# Project_MachNguon.net
KiCad netlist of a schematic drawn in Altium Designer
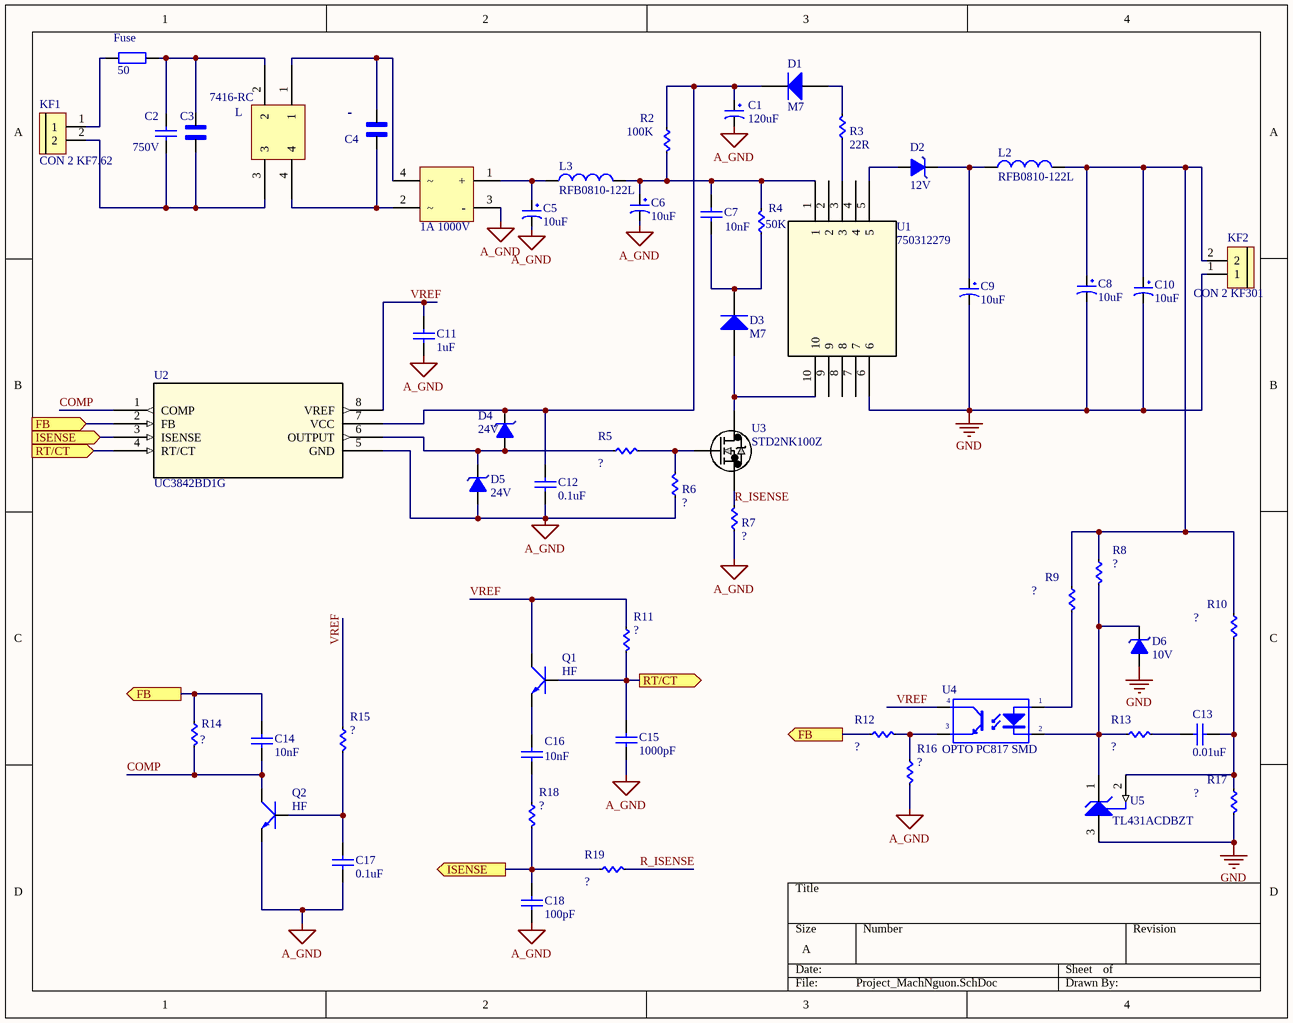
[diagram p0: Project_MachNguon.SchDoc]

(export (version "E")
  (design (tool "Eeschema 10.0.6"))
  (components
    (comp (ref "1")
      (value "1A 1000V")
      (footprint "DIODE CAU 1A SMD SOP4")
      (description "Dán")
      (libsource (lib "Altium_Lib_by_KhueNguyenCreator") (part "Diode CAU 1A SMD"))
    )
    (comp (ref "C1")
      (value "120uF")
      (footprint "tu hoa 5mm")
      (description "Cắm")
      (libsource (lib "Altium_Lib_by_KhueNguyenCreator") (part "Tu Hoa 100uF 25V 6x11"))
    )
    (comp (ref "C2")
      (value "750V")
      (footprint "tu tantalum dip5.08")
      (description "Cắm")
      (libsource (lib "Altium_Lib_by_KhueNguyenCreator") (part "Tu tantalum 100pF DIP5.08"))
    )
    (comp (ref "C3")
      (value "B32923P3155K000")
      (footprint "CAPRR2250W80L2650T1450H2950")
      (description "SUPPRESSION CAP, 1.5UF, CLASS X2, 305VAC ROHS COMPLIANT: YES")
      (fields (field (name "MF") "TDK Electronics"))
      (libsource (lib "Hung_lib") (part "B32923P3155K000"))
    )
    (comp (ref "C4")
      (value "B32923P3155K000")
      (footprint "CAPRR2250W80L2650T1450H2950")
      (description "SUPPRESSION CAP, 1.5UF, CLASS X2, 305VAC ROHS COMPLIANT: YES")
      (fields (field (name "MF") "TDK Electronics"))
      (libsource (lib "Hung_lib") (part "B32923P3155K000"))
    )
    (comp (ref "C5")
      (value "10uF")
      (footprint "tu Hoa 18mm")
      (description "Cắm")
      (libsource (lib "Altium_Lib_by_KhueNguyenCreator") (part "Tu Hoa 100uF 450V 18x35"))
    )
    (comp (ref "C6")
      (value "10uF")
      (footprint "tu Hoa 18mm")
      (description "Cắm")
      (libsource (lib "Altium_Lib_by_KhueNguyenCreator") (part "Tu Hoa 100uF 450V 18x35"))
    )
    (comp (ref "C7")
      (value "10nF")
      (footprint "tu 0603")
      (description "Dán")
      (libsource (lib "Altium_Lib_by_KhueNguyenCreator") (part "Tu 0603 105 50V 10%"))
    )
    (comp (ref "C8")
      (value "10uF")
      (footprint "tu hoa 10mm")
      (description "Cắm")
      (libsource (lib "Altium_Lib_by_KhueNguyenCreator") (part "Tu Hoa 1000uF 10V 10x12"))
    )
    (comp (ref "C9")
      (value "10uF")
      (footprint "tu hoa 10mm")
      (description "Cắm")
      (libsource (lib "Altium_Lib_by_KhueNguyenCreator") (part "Tu Hoa 1000uF 10V 10x12"))
    )
    (comp (ref "C10")
      (value "10uF")
      (footprint "tu hoa 10mm")
      (description "Cắm")
      (libsource (lib "Altium_Lib_by_KhueNguyenCreator") (part "Tu Hoa 1000uF 10V 10x12"))
    )
    (comp (ref "C11")
      (value "1uF")
      (footprint "tu 0603")
      (description "Dán")
      (libsource (lib "Altium_Lib_by_KhueNguyenCreator") (part "Tu 0603 101 50V 10%"))
    )
    (comp (ref "C12")
      (value "0.1uF")
      (footprint "tu 0603")
      (description "Dán")
      (libsource (lib "Altium_Lib_by_KhueNguyenCreator") (part "Tu 0603 101 50V 10%"))
    )
    (comp (ref "C13")
      (value "0.01uF")
      (footprint "tu 0603")
      (description "Dán")
      (libsource (lib "Altium_Lib_by_KhueNguyenCreator") (part "Tu 0603 101 50V 10%"))
    )
    (comp (ref "C14")
      (value "10nF")
      (footprint "tu 0603")
      (description "Dán")
      (libsource (lib "Altium_Lib_by_KhueNguyenCreator") (part "Tu 0603 101 50V 10%"))
    )
    (comp (ref "C15")
      (value "1000pF")
      (footprint "tu 0603")
      (description "Dán")
      (libsource (lib "Altium_Lib_by_KhueNguyenCreator") (part "Tu 0603 101 50V 10%"))
    )
    (comp (ref "C16")
      (value "10nF")
      (footprint "tu 0603")
      (description "Dán")
      (libsource (lib "Altium_Lib_by_KhueNguyenCreator") (part "Tu 0603 101 50V 10%"))
    )
    (comp (ref "C17")
      (value "0.1uF")
      (footprint "tu 0603")
      (description "Dán")
      (libsource (lib "Altium_Lib_by_KhueNguyenCreator") (part "Tu 0603 101 50V 10%"))
    )
    (comp (ref "C18")
      (value "100pF")
      (footprint "tu 0603")
      (description "Dán")
      (libsource (lib "Altium_Lib_by_KhueNguyenCreator") (part "Tu 0603 101 50V 10%"))
    )
    (comp (ref "D1")
      (value "M7")
      (footprint "DIODE SMA")
      (description "Dán")
      (libsource (lib "Altium_Lib_by_KhueNguyenCreator") (part "Diode M7 ( 4007 )"))
    )
    (comp (ref "D2")
      (value "12V")
      (footprint "DIODE ZENNER SMD SOD80")
      (description "Dán")
      (libsource (lib "Altium_Lib_by_KhueNguyenCreator") (part "Diode Zener 12V"))
    )
    (comp (ref "D3")
      (value "M7")
      (footprint "DIODE SMA")
      (description "Dán")
      (libsource (lib "Altium_Lib_by_KhueNguyenCreator") (part "Diode M7 ( 4007 )"))
    )
    (comp (ref "D4")
      (value "24V")
      (footprint "DIODE ZENNER SMD SOD80")
      (description "Cắm")
      (libsource (lib "Altium_Lib_by_KhueNguyenCreator") (part "Diode Zener 24V"))
    )
    (comp (ref "D5")
      (value "24V")
      (footprint "DIODE ZENNER SMD SOD80")
      (description "Cắm")
      (libsource (lib "Altium_Lib_by_KhueNguyenCreator") (part "Diode Zener 24V"))
    )
    (comp (ref "D6")
      (value "10V")
      (footprint "DIODE ZENNER SMD SOD80")
      (description "Dán")
      (libsource (lib "Altium_Lib_by_KhueNguyenCreator") (part "Diode Zener 12V"))
    )
    (comp (ref "Fuse")
      (value "50")
      (footprint "tro vach 2w")
      (description "Cắm")
      (libsource (lib "Altium_Lib_by_KhueNguyenCreator") (part "Tro Vach 2W 5% 100R"))
    )
    (comp (ref "KF1")
      (value "CON 2 KF7.62")
      (footprint "CON 2 KF7.62")
      (description "Cắm")
      (libsource (lib "Altium_Lib_by_KhueNguyenCreator") (part "CON 2 KF7.62"))
    )
    (comp (ref "KF2")
      (value "CON 2 KF301")
      (footprint "Con 2 KF301 5.08")
      (description "Cắm")
      (libsource (lib "Altium_Lib_by_KhueNguyenCreator") (part "CON 2 KF301"))
    )
    (comp (ref "L") (value "7416-RC") (footprint "7416-RC") (libsource (lib "Hung_lib") (part "7416-RC")))
    (comp (ref "L2")
      (value "RFB0810-122L")
      (footprint "IND_P220_D378_H452_70X59_TH")
      (description "Fixed Inductors RFB0810 AEC-Q200 100kHz 2.8mOhms")
      (fields (field (name "MANUFACTURER") "Coilcraft"))
      (libsource (lib "Altium_Lib_by_KhueNguyenCreator") (part "IND_1.2mH-0.47A-10%-TH"))
    )
    (comp (ref "L3")
      (value "RFB0810-122L")
      (footprint "IND_P220_D378_H452_70X59_TH")
      (description "Fixed Inductors RFB0810 AEC-Q200 100kHz 2.8mOhms")
      (fields (field (name "MANUFACTURER") "Coilcraft"))
      (libsource (lib "Altium_Lib_by_KhueNguyenCreator") (part "IND_1.2mH-0.47A-10%-TH"))
    )
    (comp (ref "Q1")
      (value "HF")
      (footprint "SOT-23")
      (description "SOT-23")
      (libsource (lib "Altium_Lib_by_KhueNguyenCreator") (part "Trans C1815 HF SMD"))
    )
    (comp (ref "Q2")
      (value "HF")
      (footprint "SOT-23")
      (description "SOT-23")
      (libsource (lib "Altium_Lib_by_KhueNguyenCreator") (part "Trans C1815 HF SMD"))
    )
    (comp (ref "R2")
      (value "100K")
      (footprint "RES 1206")
      (description "RES SMD 1206")
      (fields
        (field (name "MANUFACTURER") "Vishay Dale")
        (field (name "MANUFACTURER PART NUMBER") "CRCW040210K0FKED")
      )
      (libsource (lib "Altium_Lib_by_KhueNguyenCreator") (part "RES 1206"))
    )
    (comp (ref "R3")
      (value "22R")
      (footprint "RES 1206")
      (description "RES SMD 1206")
      (fields
        (field (name "MANUFACTURER") "Vishay Dale")
        (field (name "MANUFACTURER PART NUMBER") "CRCW040210K0FKED")
      )
      (libsource (lib "Altium_Lib_by_KhueNguyenCreator") (part "RES 1206"))
    )
    (comp (ref "R4")
      (value "50K")
      (footprint "RES 1206")
      (description "RES SMD 1206")
      (fields
        (field (name "MANUFACTURER") "Vishay Dale")
        (field (name "MANUFACTURER PART NUMBER") "CRCW040210K0FKED")
      )
      (libsource (lib "Altium_Lib_by_KhueNguyenCreator") (part "RES 1206"))
    )
    (comp (ref "R5")
      (value "?")
      (footprint "RES 0603")
      (description "RES SMD 0603")
      (fields
        (field (name "MANUFACTURER") "Vishay Dale")
        (field (name "MANUFACTURER PART NUMBER") "CRCW040210K0FKED")
      )
      (libsource (lib "Altium_Lib_by_KhueNguyenCreator") (part "RES 0603"))
    )
    (comp (ref "R6")
      (value "?")
      (footprint "RES 0603")
      (description "RES SMD 0603")
      (fields
        (field (name "MANUFACTURER") "Vishay Dale")
        (field (name "MANUFACTURER PART NUMBER") "CRCW040210K0FKED")
      )
      (libsource (lib "Altium_Lib_by_KhueNguyenCreator") (part "RES 0603"))
    )
    (comp (ref "R7")
      (value "?")
      (footprint "RES 0603")
      (description "RES SMD 0603")
      (fields
        (field (name "MANUFACTURER") "Vishay Dale")
        (field (name "MANUFACTURER PART NUMBER") "CRCW040210K0FKED")
      )
      (libsource (lib "Altium_Lib_by_KhueNguyenCreator") (part "RES 0603"))
    )
    (comp (ref "R8")
      (value "?")
      (footprint "RES 0603")
      (description "RES SMD 0603")
      (fields
        (field (name "MANUFACTURER") "Vishay Dale")
        (field (name "MANUFACTURER PART NUMBER") "CRCW040210K0FKED")
      )
      (libsource (lib "Altium_Lib_by_KhueNguyenCreator") (part "RES 0603"))
    )
    (comp (ref "R9")
      (value "?")
      (footprint "RES 0603")
      (description "RES SMD 0603")
      (fields
        (field (name "MANUFACTURER") "Vishay Dale")
        (field (name "MANUFACTURER PART NUMBER") "CRCW040210K0FKED")
      )
      (libsource (lib "Altium_Lib_by_KhueNguyenCreator") (part "RES 0603"))
    )
    (comp (ref "R10")
      (value "?")
      (footprint "RES 0603")
      (description "RES SMD 0603")
      (fields
        (field (name "MANUFACTURER") "Vishay Dale")
        (field (name "MANUFACTURER PART NUMBER") "CRCW040210K0FKED")
      )
      (libsource (lib "Altium_Lib_by_KhueNguyenCreator") (part "RES 0603"))
    )
    (comp (ref "R11")
      (value "?")
      (footprint "RES 0603")
      (description "RES SMD 0603")
      (fields
        (field (name "MANUFACTURER") "Vishay Dale")
        (field (name "MANUFACTURER PART NUMBER") "CRCW040210K0FKED")
      )
      (libsource (lib "Altium_Lib_by_KhueNguyenCreator") (part "RES 0603"))
    )
    (comp (ref "R12")
      (value "?")
      (footprint "RES 0603")
      (description "RES SMD 0603")
      (fields
        (field (name "MANUFACTURER") "Vishay Dale")
        (field (name "MANUFACTURER PART NUMBER") "CRCW040210K0FKED")
      )
      (libsource (lib "Altium_Lib_by_KhueNguyenCreator") (part "RES 0603"))
    )
    (comp (ref "R13")
      (value "?")
      (footprint "RES 0603")
      (description "RES SMD 0603")
      (fields
        (field (name "MANUFACTURER") "Vishay Dale")
        (field (name "MANUFACTURER PART NUMBER") "CRCW040210K0FKED")
      )
      (libsource (lib "Altium_Lib_by_KhueNguyenCreator") (part "RES 0603"))
    )
    (comp (ref "R14")
      (value "?")
      (footprint "RES 0603")
      (description "RES SMD 0603")
      (fields
        (field (name "MANUFACTURER") "Vishay Dale")
        (field (name "MANUFACTURER PART NUMBER") "CRCW040210K0FKED")
      )
      (libsource (lib "Altium_Lib_by_KhueNguyenCreator") (part "RES 0603"))
    )
    (comp (ref "R15")
      (value "?")
      (footprint "RES 0603")
      (description "RES SMD 0603")
      (fields
        (field (name "MANUFACTURER") "Vishay Dale")
        (field (name "MANUFACTURER PART NUMBER") "CRCW040210K0FKED")
      )
      (libsource (lib "Altium_Lib_by_KhueNguyenCreator") (part "RES 0603"))
    )
    (comp (ref "R16")
      (value "?")
      (footprint "RES 0603")
      (description "RES SMD 0603")
      (fields
        (field (name "MANUFACTURER") "Vishay Dale")
        (field (name "MANUFACTURER PART NUMBER") "CRCW040210K0FKED")
      )
      (libsource (lib "Altium_Lib_by_KhueNguyenCreator") (part "RES 0603"))
    )
    (comp (ref "R17")
      (value "?")
      (footprint "RES 0603")
      (description "RES SMD 0603")
      (fields
        (field (name "MANUFACTURER") "Vishay Dale")
        (field (name "MANUFACTURER PART NUMBER") "CRCW040210K0FKED")
      )
      (libsource (lib "Altium_Lib_by_KhueNguyenCreator") (part "RES 0603"))
    )
    (comp (ref "R18")
      (value "?")
      (footprint "RES 0603")
      (description "RES SMD 0603")
      (fields
        (field (name "MANUFACTURER") "Vishay Dale")
        (field (name "MANUFACTURER PART NUMBER") "CRCW040210K0FKED")
      )
      (libsource (lib "Altium_Lib_by_KhueNguyenCreator") (part "RES 0603"))
    )
    (comp (ref "R19")
      (value "?")
      (footprint "RES 0603")
      (description "RES SMD 0603")
      (fields
        (field (name "MANUFACTURER") "Vishay Dale")
        (field (name "MANUFACTURER PART NUMBER") "CRCW040210K0FKED")
      )
      (libsource (lib "Altium_Lib_by_KhueNguyenCreator") (part "RES 0603"))
    )
    (comp (ref "U1")
      (value "750312279")
      (footprint "750312279_WRE")
      (description "Description")
      (fields (field (name "COPYRIGHT") "Copyright (C) 2025 Ultra Librarian. All rights reserved."))
      (libsource (lib "Hung_lib") (part "750312279"))
    )
    (comp (ref "U2")
      (value "UC3842BD1G")
      (footprint "SOIC8_ONS-L")
      (description "No Description Available")
      (fields (field (name "COPYRIGHT") "Copyright (C) 2025 Ultra Librarian. All rights reserved."))
      (libsource (lib "Hung_lib") (part "UC3842BD1G"))
    )
    (comp (ref "U3")
      (value "STD2NK100Z")
      (footprint "DPAK_STM-L")
      (description "N-channel 1000 V, 6.25 Ohm typ., 1.85 A SuperMESH Power MOSFET in a DPAK package")
      (fields (field (name "COPYRIGHT") "Copyright (C) 2025 Ultra Librarian. All rights reserved."))
      (libsource (lib "Hung_lib") (part "STD2NK100Z"))
    )
    (comp (ref "U4")
      (value "OPTO PC817 SMD")
      (footprint "SOP4")
      (description "Single Opto")
      (libsource (lib "Altium_Lib_by_KhueNguyenCreator") (part "OPTO PC817 SMD"))
    )
    (comp (ref "U5")
      (value "TL431ACDBZT")
      (footprint "SOT 23-3")
      (description "Shunt Voltage Reference IC 36V ±1% SOT-23-3")
      (fields (field (name "MANUFACTURER") "Texas Instruments"))
      (libsource (lib "Altium_Lib_by_KhueNguyenCreator") (part "IC_TL431ACDBZT"))
    )
  )
  (nets
    (net (code "1") (name "/COMP") (class "Default")
      (node (ref "C14") (pin "1") (pinfunction "1_1") (pintype "passive"))
      (node (ref "Q2") (pin "3") (pinfunction "C_3") (pintype "passive"))
      (node (ref "R14") (pin "2") (pinfunction "2_2") (pintype "passive"))
      (node (ref "U2") (pin "1") (pinfunction "COMP_1") (pintype "output"))
    )
    (net (code "2") (name "/FB") (class "Default")
      (node (ref "C14") (pin "2") (pinfunction "2_2") (pintype "passive"))
      (node (ref "R12") (pin "1") (pinfunction "1_1") (pintype "passive"))
      (node (ref "R14") (pin "1") (pinfunction "1_1") (pintype "passive"))
      (node (ref "U2") (pin "2") (pinfunction "FB_2") (pintype "input"))
    )
    (net (code "3") (name "/ISENSE") (class "Default")
      (node (ref "C18") (pin "1") (pinfunction "1_1") (pintype "passive"))
      (node (ref "R18") (pin "2") (pinfunction "2_2") (pintype "passive"))
      (node (ref "R19") (pin "1") (pinfunction "1_1") (pintype "passive"))
      (node (ref "U2") (pin "3") (pinfunction "ISENSE_3") (pintype "input"))
    )
    (net (code "4") (name "/RT{slash}CT") (class "Default")
      (node (ref "C15") (pin "2") (pinfunction "2_2") (pintype "passive"))
      (node (ref "Q1") (pin "1") (pinfunction "B_1") (pintype "passive"))
      (node (ref "R11") (pin "2") (pinfunction "2_2") (pintype "passive"))
      (node (ref "U2") (pin "4") (pinfunction "RT/CT_4") (pintype "input"))
    )
    (net (code "5") (name "/R_ISENSE") (class "Default")
      (node (ref "R19") (pin "2") (pinfunction "2_2") (pintype "passive"))
      (node (ref "R7") (pin "2") (pinfunction "2_2") (pintype "passive"))
      (node (ref "U3") (pin "2") (pinfunction "3_2") (pintype "passive"))
    )
    (net (code "6") (name "/VREF") (class "Default")
      (node (ref "C11") (pin "1") (pinfunction "1_1") (pintype "passive"))
      (node (ref "Q1") (pin "3") (pinfunction "C_3") (pintype "passive"))
      (node (ref "R11") (pin "1") (pinfunction "1_1") (pintype "passive"))
      (node (ref "R15") (pin "1") (pinfunction "1_1") (pintype "passive"))
      (node (ref "U2") (pin "8") (pinfunction "VREF_8") (pintype "output"))
      (node (ref "U4") (pin "4") (pinfunction "C_4") (pintype "passive"))
    )
    (net (code "7") (name "A_GND") (class "Default")
      (node (ref "1") (pin "3") (pinfunction "-_3") (pintype "passive"))
      (node (ref "C1") (pin "2") (pinfunction "2_2") (pintype "passive"))
      (node (ref "C11") (pin "2") (pinfunction "2_2") (pintype "passive"))
      (node (ref "C12") (pin "2") (pinfunction "2_2") (pintype "passive"))
      (node (ref "C15") (pin "1") (pinfunction "1_1") (pintype "passive"))
      (node (ref "C17") (pin "1") (pinfunction "1_1") (pintype "passive"))
      (node (ref "C18") (pin "2") (pinfunction "2_2") (pintype "passive"))
      (node (ref "C5") (pin "2") (pinfunction "2_2") (pintype "passive"))
      (node (ref "C6") (pin "2") (pinfunction "2_2") (pintype "passive"))
      (node (ref "D5") (pin "1") (pinfunction "A_1") (pintype "passive"))
      (node (ref "Q2") (pin "2") (pinfunction "E_2") (pintype "passive"))
      (node (ref "R16") (pin "2") (pinfunction "2_2") (pintype "passive"))
      (node (ref "R6") (pin "1") (pinfunction "1_1") (pintype "passive"))
      (node (ref "R7") (pin "1") (pinfunction "1_1") (pintype "passive"))
      (node (ref "U2") (pin "5") (pinfunction "GND_5") (pintype "power_in"))
    )
    (net (code "8") (name "GND") (class "Default")
      (node (ref "C10") (pin "2") (pinfunction "2_2") (pintype "passive"))
      (node (ref "C8") (pin "2") (pinfunction "2_2") (pintype "passive"))
      (node (ref "C9") (pin "2") (pinfunction "2_2") (pintype "passive"))
      (node (ref "D6") (pin "1") (pinfunction "A_1") (pintype "passive"))
      (node (ref "KF2") (pin "1") (pinfunction "1_1") (pintype "passive"))
      (node (ref "R17") (pin "2") (pinfunction "2_2") (pintype "passive"))
      (node (ref "U1") (pin "6") (pinfunction "6_6") (pintype "passive"))
      (node (ref "U5") (pin "3") (pinfunction "ANODE_3") (pintype "passive"))
    )
    (net (code "9") (name "Net-(1-+)") (class "Default")
      (node (ref "1") (pin "1") (pinfunction "+_1") (pintype "passive"))
      (node (ref "C5") (pin "1") (pinfunction "1_1") (pintype "passive"))
      (node (ref "L3") (pin "1") (pinfunction "1_1") (pintype "passive"))
    )
    (net (code "10") (name "Net-(1-~-Pad2)") (class "Default")
      (node (ref "1") (pin "2") (pinfunction "~_2") (pintype "passive"))
      (node (ref "C4") (pin "1") (pinfunction "1_1") (pintype "passive"))
      (node (ref "L") (pin "4") (pinfunction "4_4") (pintype "passive"))
    )
    (net (code "11") (name "Net-(1-~-Pad4)") (class "Default")
      (node (ref "1") (pin "4") (pinfunction "~_4") (pintype "passive"))
      (node (ref "C4") (pin "2") (pinfunction "2_2") (pintype "passive"))
      (node (ref "L") (pin "1") (pinfunction "1_1") (pintype "passive"))
    )
    (net (code "12") (name "Net-(C2-Pad1)") (class "Default")
      (node (ref "C2") (pin "1") (pinfunction "1_1") (pintype "passive"))
      (node (ref "C3") (pin "2") (pinfunction "2_2") (pintype "passive"))
      (node (ref "Fuse") (pin "2") (pinfunction "2_2") (pintype "passive"))
      (node (ref "L") (pin "2") (pinfunction "2_2") (pintype "passive"))
    )
    (net (code "13") (name "Net-(C2-Pad2)") (class "Default")
      (node (ref "C2") (pin "2") (pinfunction "2_2") (pintype "passive"))
      (node (ref "C3") (pin "1") (pinfunction "1_1") (pintype "passive"))
      (node (ref "KF1") (pin "2") (pinfunction "2_2") (pintype "passive"))
      (node (ref "L") (pin "3") (pinfunction "3_3") (pintype "passive"))
    )
    (net (code "14") (name "Net-(C6-Pad1)") (class "Default")
      (node (ref "C6") (pin "1") (pinfunction "1_1") (pintype "passive"))
      (node (ref "C7") (pin "1") (pinfunction "1_1") (pintype "passive"))
      (node (ref "L3") (pin "2") (pinfunction "2_2") (pintype "passive"))
      (node (ref "R2") (pin "2") (pinfunction "2_2") (pintype "passive"))
      (node (ref "R4") (pin "2") (pinfunction "2_2") (pintype "passive"))
      (node (ref "U1") (pin "1") (pinfunction "1_1") (pintype "passive"))
    )
    (net (code "15") (name "Net-(C10-Pad1)") (class "Default")
      (node (ref "C10") (pin "1") (pinfunction "1_1") (pintype "passive"))
      (node (ref "C8") (pin "1") (pinfunction "1_1") (pintype "passive"))
      (node (ref "KF2") (pin "2") (pinfunction "2_2") (pintype "passive"))
      (node (ref "L2") (pin "2") (pinfunction "2_2") (pintype "passive"))
      (node (ref "R10") (pin "1") (pinfunction "1_1") (pintype "passive"))
      (node (ref "R8") (pin "1") (pinfunction "1_1") (pintype "passive"))
      (node (ref "R9") (pin "1") (pinfunction "1_1") (pintype "passive"))
    )
    (net (code "16") (name "Net-(C13-Pad2)") (class "Default")
      (node (ref "C13") (pin "2") (pinfunction "2_2") (pintype "passive"))
      (node (ref "R13") (pin "2") (pinfunction "2_2") (pintype "passive"))
    )
    (net (code "17") (name "Net-(C16-Pad1)") (class "Default")
      (node (ref "C16") (pin "1") (pinfunction "1_1") (pintype "passive"))
      (node (ref "R18") (pin "1") (pinfunction "1_1") (pintype "passive"))
    )
    (net (code "18") (name "Net-(D1-A)") (class "Default")
      (node (ref "D1") (pin "1") (pinfunction "A_1") (pintype "passive"))
      (node (ref "R3") (pin "2") (pinfunction "2_2") (pintype "passive"))
    )
    (net (code "19") (name "Net-(D1-K)") (class "Default")
      (node (ref "C1") (pin "1") (pinfunction "1_1") (pintype "passive"))
      (node (ref "C12") (pin "1") (pinfunction "1_1") (pintype "passive"))
      (node (ref "D1") (pin "2") (pinfunction "K_2") (pintype "passive"))
      (node (ref "D4") (pin "2") (pinfunction "K_2") (pintype "passive"))
      (node (ref "R2") (pin "1") (pinfunction "1_1") (pintype "passive"))
      (node (ref "U2") (pin "7") (pinfunction "VCC_7") (pintype "power_in"))
    )
    (net (code "20") (name "Net-(D2-A)") (class "Default")
      (node (ref "D2") (pin "1") (pinfunction "A_1") (pintype "passive"))
      (node (ref "U1") (pin "5") (pinfunction "5_5") (pintype "passive"))
    )
    (net (code "21") (name "Net-(D2-K)") (class "Default")
      (node (ref "C9") (pin "1") (pinfunction "1_1") (pintype "passive"))
      (node (ref "D2") (pin "2") (pinfunction "K_2") (pintype "passive"))
      (node (ref "L2") (pin "1") (pinfunction "1_1") (pintype "passive"))
    )
    (net (code "22") (name "Net-(D3-A)") (class "Default")
      (node (ref "D3") (pin "1") (pinfunction "A_1") (pintype "passive"))
      (node (ref "U1") (pin "10") (pinfunction "10_10") (pintype "passive"))
      (node (ref "U3") (pin "3") (pinfunction "2_3") (pintype "passive"))
    )
    (net (code "23") (name "Net-(D3-K)") (class "Default")
      (node (ref "C7") (pin "2") (pinfunction "2_2") (pintype "passive"))
      (node (ref "D3") (pin "2") (pinfunction "K_2") (pintype "passive"))
      (node (ref "R4") (pin "1") (pinfunction "1_1") (pintype "passive"))
    )
    (net (code "24") (name "Net-(D4-A)") (class "Default")
      (node (ref "D4") (pin "1") (pinfunction "A_1") (pintype "passive"))
      (node (ref "D5") (pin "2") (pinfunction "K_2") (pintype "passive"))
      (node (ref "R5") (pin "1") (pinfunction "1_1") (pintype "passive"))
      (node (ref "U2") (pin "6") (pinfunction "OUTPUT_6") (pintype "output"))
    )
    (net (code "25") (name "Net-(D6-K)") (class "Default")
      (node (ref "D6") (pin "2") (pinfunction "K_2") (pintype "passive"))
      (node (ref "R13") (pin "1") (pinfunction "1_1") (pintype "passive"))
      (node (ref "R8") (pin "2") (pinfunction "2_2") (pintype "passive"))
      (node (ref "U4") (pin "2") (pinfunction "K_2") (pintype "passive"))
      (node (ref "U5") (pin "1") (pinfunction "CATHODE_1") (pintype "passive"))
    )
    (net (code "26") (name "Net-(Fuse-Pad1)") (class "Default")
      (node (ref "Fuse") (pin "1") (pinfunction "1_1") (pintype "passive"))
      (node (ref "KF1") (pin "1") (pinfunction "1_1") (pintype "passive"))
    )
    (net (code "27") (name "Net-(Q1-E)") (class "Default")
      (node (ref "C16") (pin "2") (pinfunction "2_2") (pintype "passive"))
      (node (ref "Q1") (pin "2") (pinfunction "E_2") (pintype "passive"))
    )
    (net (code "28") (name "Net-(Q2-B)") (class "Default")
      (node (ref "C17") (pin "2") (pinfunction "2_2") (pintype "passive"))
      (node (ref "Q2") (pin "1") (pinfunction "B_1") (pintype "passive"))
      (node (ref "R15") (pin "2") (pinfunction "2_2") (pintype "passive"))
    )
    (net (code "29") (name "Net-(R3-Pad1)") (class "Default")
      (node (ref "R3") (pin "1") (pinfunction "1_1") (pintype "passive"))
      (node (ref "U1") (pin "3") (pinfunction "3_3") (pintype "passive"))
    )
    (net (code "30") (name "Net-(R5-Pad2)") (class "Default")
      (node (ref "R5") (pin "2") (pinfunction "2_2") (pintype "passive"))
      (node (ref "R6") (pin "2") (pinfunction "2_2") (pintype "passive"))
      (node (ref "U3") (pin "1") (pinfunction "1_1") (pintype "passive"))
    )
    (net (code "31") (name "Net-(U4-A)") (class "Default")
      (node (ref "R9") (pin "2") (pinfunction "2_2") (pintype "passive"))
      (node (ref "U4") (pin "1") (pinfunction "A_1") (pintype "passive"))
    )
    (net (code "32") (name "Net-(U4-E)") (class "Default")
      (node (ref "R12") (pin "2") (pinfunction "2_2") (pintype "passive"))
      (node (ref "R16") (pin "1") (pinfunction "1_1") (pintype "passive"))
      (node (ref "U4") (pin "3") (pinfunction "E_3") (pintype "passive"))
    )
    (net (code "33") (name "Net-(U5-REF)") (class "Default")
      (node (ref "C13") (pin "1") (pinfunction "1_1") (pintype "passive"))
      (node (ref "R10") (pin "2") (pinfunction "2_2") (pintype "passive"))
      (node (ref "R17") (pin "1") (pinfunction "1_1") (pintype "passive"))
      (node (ref "U5") (pin "2") (pinfunction "REF_2") (pintype "input"))
    )
    (net (code "34") (name "unconnected-(U1-Pad2)") (class "Default")
      (node (ref "U1") (pin "2") (pinfunction "2_2") (pintype "passive"))
    )
    (net (code "35") (name "unconnected-(U1-Pad4)") (class "Default")
      (node (ref "U1") (pin "4") (pinfunction "4_4") (pintype "passive"))
    )
    (net (code "36") (name "unconnected-(U1-Pad7)") (class "Default")
      (node (ref "U1") (pin "7") (pinfunction "7_7") (pintype "passive"))
    )
    (net (code "37") (name "unconnected-(U1-Pad8)") (class "Default")
      (node (ref "U1") (pin "8") (pinfunction "8_8") (pintype "passive"))
    )
    (net (code "38") (name "unconnected-(U1-Pad9)") (class "Default")
      (node (ref "U1") (pin "9") (pinfunction "9_9") (pintype "passive"))
    )
  )
)
